# Sheet1.net
KiCad netlist of a schematic drawn in Altium Designer
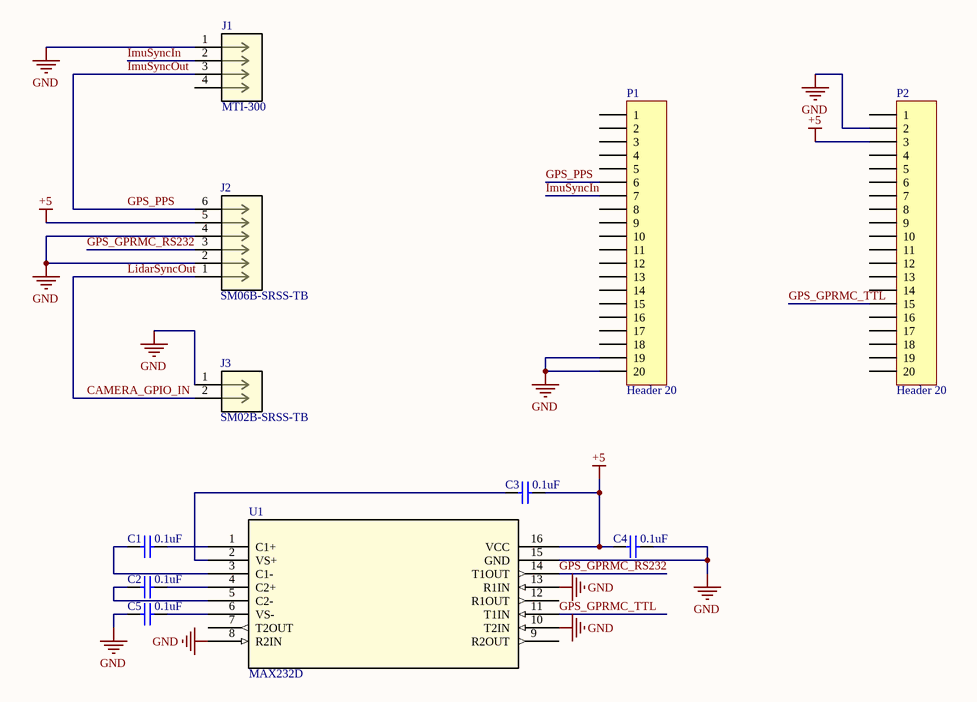
[diagram p0: Sheet1.SchDoc]

(export (version "E")
  (design (tool "Eeschema 10.0.6"))
  (components
    (comp (ref "C1")
      (value "0.1uF")
      (footprint "6-0805_N")
      (description "Capacitor")
      (fields (field (name "Comment") "Cap") (field (name "PUBLISHER") "Altium Limited"))
      (libsource (lib "Miscellaneous Devices") (part "Cap"))
    )
    (comp (ref "C2")
      (value "0.1uF")
      (footprint "6-0805_N")
      (description "Capacitor")
      (fields (field (name "Comment") "Cap") (field (name "PUBLISHER") "Altium Limited"))
      (libsource (lib "Miscellaneous Devices") (part "Cap"))
    )
    (comp (ref "C3")
      (value "0.1uF")
      (footprint "6-0805_N")
      (description "Capacitor")
      (fields (field (name "Comment") "Cap") (field (name "PUBLISHER") "Altium Limited"))
      (libsource (lib "Miscellaneous Devices") (part "Cap"))
    )
    (comp (ref "C4")
      (value "0.1uF")
      (footprint "6-0805_N")
      (description "Capacitor")
      (fields (field (name "Comment") "Cap") (field (name "PUBLISHER") "Altium Limited"))
      (libsource (lib "Miscellaneous Devices") (part "Cap"))
    )
    (comp (ref "C5")
      (value "0.1uF")
      (footprint "6-0805_N")
      (description "Capacitor")
      (fields (field (name "Comment") "Cap") (field (name "PUBLISHER") "Altium Limited"))
      (libsource (lib "Miscellaneous Devices") (part "Cap"))
    )
    (comp (ref "J1")
      (value "MTI-300")
      (footprint "CONN_SM04B-SRSS-TB_JST")
      (description "No Description Available")
      (libsource (lib "SM04B-SRSS-TB") (part "SM04B-SRSS-TB"))
    )
    (comp (ref "J2")
      (value "SM06B-SRSS-TB")
      (footprint "CONN_SM06B-SRSS-TB_JST")
      (description "No Description Available")
      (libsource (lib "SM06B-SRSS-TBLFSN") (part "SM06B-SRSS-TBLFSN"))
    )
    (comp (ref "J3")
      (value "SM02B-SRSS-TB")
      (footprint "CONN_SM02B-SRSS-TB_JST")
      (description "No Description Available")
      (libsource (lib "SM02B-SRSS-TB") (part "SM02B-SRSS-TB"))
    )
    (comp (ref "P1")
      (value "Header 20")
      (footprint "HDR1X20")
      (description "Header, 20-Pin")
      (fields (field (name "PUBLISHER") "Altium Limited"))
      (libsource (lib "Miscellaneous Connectors") (part "Header 20"))
    )
    (comp (ref "P2")
      (value "Header 20")
      (footprint "HDR1X20")
      (description "Header, 20-Pin")
      (fields (field (name "PUBLISHER") "Altium Limited"))
      (libsource (lib "Miscellaneous Connectors") (part "Header 20"))
    )
    (comp (ref "U1")
      (value "MAX232D")
      (footprint "D16")
      (description "No Description Available")
      (libsource (lib "MAX232D") (part "MAX232D"))
    )
  )
  (nets
    (net (code "1") (name "+5") (class "Default")
      (node (ref "C3") (pin "1") (pinfunction "1_1") (pintype "passive"))
      (node (ref "C4") (pin "2") (pinfunction "2_2") (pintype "passive"))
      (node (ref "J2") (pin "5") (pinfunction "5_5") (pintype "passive"))
      (node (ref "P2") (pin "3") (pinfunction "3_3") (pintype "passive"))
      (node (ref "U1") (pin "16") (pinfunction "VCC_16") (pintype "power_in"))
    )
    (net (code "2") (name "/CAMERA_GPIO_IN") (class "Default")
      (node (ref "J2") (pin "1") (pinfunction "1_1") (pintype "passive"))
      (node (ref "J3") (pin "2") (pinfunction "2_2") (pintype "passive"))
    )
    (net (code "3") (name "/GPS_GPRMC_RS232") (class "Default")
      (node (ref "J2") (pin "3") (pinfunction "3_3") (pintype "passive"))
      (node (ref "U1") (pin "14") (pinfunction "T1OUT_14") (pintype "output"))
    )
    (net (code "4") (name "/GPS_GPRMC_TTL") (class "Default")
      (node (ref "P2") (pin "15") (pinfunction "15_15") (pintype "passive"))
      (node (ref "U1") (pin "11") (pinfunction "T1IN_11") (pintype "input"))
    )
    (net (code "5") (name "/GPS_PPS") (class "Default")
      (node (ref "J1") (pin "3") (pinfunction "3_3") (pintype "passive"))
      (node (ref "J2") (pin "6") (pinfunction "6_6") (pintype "passive"))
      (node (ref "P1") (pin "6") (pinfunction "6_6") (pintype "passive"))
    )
    (net (code "6") (name "/ImuSyncIn") (class "Default")
      (node (ref "J1") (pin "2") (pinfunction "2_2") (pintype "passive"))
      (node (ref "P1") (pin "7") (pinfunction "7_7") (pintype "passive"))
    )
    (net (code "7") (name "GND") (class "Default")
      (node (ref "C4") (pin "1") (pinfunction "1_1") (pintype "passive"))
      (node (ref "C5") (pin "2") (pinfunction "2_2") (pintype "passive"))
      (node (ref "J1") (pin "1") (pinfunction "1_1") (pintype "passive"))
      (node (ref "J2") (pin "2") (pinfunction "2_2") (pintype "passive"))
      (node (ref "J2") (pin "4") (pinfunction "4_4") (pintype "passive"))
      (node (ref "J3") (pin "1") (pinfunction "1_1") (pintype "passive"))
      (node (ref "P1") (pin "19") (pinfunction "19_19") (pintype "passive"))
      (node (ref "P1") (pin "20") (pinfunction "20_20") (pintype "passive"))
      (node (ref "P2") (pin "2") (pinfunction "2_2") (pintype "passive"))
      (node (ref "U1") (pin "10") (pinfunction "T2IN_10") (pintype "input"))
      (node (ref "U1") (pin "13") (pinfunction "R1IN_13") (pintype "input"))
      (node (ref "U1") (pin "15") (pinfunction "GND_15") (pintype "power_in"))
      (node (ref "U1") (pin "8") (pinfunction "R2IN_8") (pintype "input"))
    )
    (net (code "8") (name "Net-(U1-C1+)") (class "Default")
      (node (ref "C1") (pin "1") (pinfunction "1_1") (pintype "passive"))
      (node (ref "U1") (pin "1") (pinfunction "C1+_1") (pintype "passive"))
    )
    (net (code "9") (name "Net-(U1-C1-)") (class "Default")
      (node (ref "C1") (pin "2") (pinfunction "2_2") (pintype "passive"))
      (node (ref "U1") (pin "3") (pinfunction "C1-_3") (pintype "passive"))
    )
    (net (code "10") (name "Net-(U1-C2+)") (class "Default")
      (node (ref "C2") (pin "1") (pinfunction "1_1") (pintype "passive"))
      (node (ref "U1") (pin "4") (pinfunction "C2+_4") (pintype "passive"))
    )
    (net (code "11") (name "Net-(U1-C2-)") (class "Default")
      (node (ref "C2") (pin "2") (pinfunction "2_2") (pintype "passive"))
      (node (ref "U1") (pin "5") (pinfunction "C2-_5") (pintype "passive"))
    )
    (net (code "12") (name "Net-(U1-VS+)") (class "Default")
      (node (ref "C3") (pin "2") (pinfunction "2_2") (pintype "passive"))
      (node (ref "U1") (pin "2") (pinfunction "VS+_2") (pintype "passive"))
    )
    (net (code "13") (name "Net-(U1-VS-)") (class "Default")
      (node (ref "C5") (pin "1") (pinfunction "1_1") (pintype "passive"))
      (node (ref "U1") (pin "6") (pinfunction "VS-_6") (pintype "passive"))
    )
    (net (code "14") (name "unconnected-(J1-Pad4)") (class "Default")
      (node (ref "J1") (pin "4") (pinfunction "4_4") (pintype "passive"))
    )
    (net (code "15") (name "unconnected-(P1-Pad1)") (class "Default")
      (node (ref "P1") (pin "1") (pinfunction "1_1") (pintype "passive"))
    )
    (net (code "16") (name "unconnected-(P1-Pad2)") (class "Default")
      (node (ref "P1") (pin "2") (pinfunction "2_2") (pintype "passive"))
    )
    (net (code "17") (name "unconnected-(P1-Pad3)") (class "Default")
      (node (ref "P1") (pin "3") (pinfunction "3_3") (pintype "passive"))
    )
    (net (code "18") (name "unconnected-(P1-Pad4)") (class "Default")
      (node (ref "P1") (pin "4") (pinfunction "4_4") (pintype "passive"))
    )
    (net (code "19") (name "unconnected-(P1-Pad5)") (class "Default")
      (node (ref "P1") (pin "5") (pinfunction "5_5") (pintype "passive"))
    )
    (net (code "20") (name "unconnected-(P1-Pad8)") (class "Default")
      (node (ref "P1") (pin "8") (pinfunction "8_8") (pintype "passive"))
    )
    (net (code "21") (name "unconnected-(P1-Pad9)") (class "Default")
      (node (ref "P1") (pin "9") (pinfunction "9_9") (pintype "passive"))
    )
    (net (code "22") (name "unconnected-(P1-Pad10)") (class "Default")
      (node (ref "P1") (pin "10") (pinfunction "10_10") (pintype "passive"))
    )
    (net (code "23") (name "unconnected-(P1-Pad11)") (class "Default")
      (node (ref "P1") (pin "11") (pinfunction "11_11") (pintype "passive"))
    )
    (net (code "24") (name "unconnected-(P1-Pad12)") (class "Default")
      (node (ref "P1") (pin "12") (pinfunction "12_12") (pintype "passive"))
    )
    (net (code "25") (name "unconnected-(P1-Pad13)") (class "Default")
      (node (ref "P1") (pin "13") (pinfunction "13_13") (pintype "passive"))
    )
    (net (code "26") (name "unconnected-(P1-Pad14)") (class "Default")
      (node (ref "P1") (pin "14") (pinfunction "14_14") (pintype "passive"))
    )
    (net (code "27") (name "unconnected-(P1-Pad15)") (class "Default")
      (node (ref "P1") (pin "15") (pinfunction "15_15") (pintype "passive"))
    )
    (net (code "28") (name "unconnected-(P1-Pad16)") (class "Default")
      (node (ref "P1") (pin "16") (pinfunction "16_16") (pintype "passive"))
    )
    (net (code "29") (name "unconnected-(P1-Pad17)") (class "Default")
      (node (ref "P1") (pin "17") (pinfunction "17_17") (pintype "passive"))
    )
    (net (code "30") (name "unconnected-(P1-Pad18)") (class "Default")
      (node (ref "P1") (pin "18") (pinfunction "18_18") (pintype "passive"))
    )
    (net (code "31") (name "unconnected-(P2-Pad1)") (class "Default")
      (node (ref "P2") (pin "1") (pinfunction "1_1") (pintype "passive"))
    )
    (net (code "32") (name "unconnected-(P2-Pad4)") (class "Default")
      (node (ref "P2") (pin "4") (pinfunction "4_4") (pintype "passive"))
    )
    (net (code "33") (name "unconnected-(P2-Pad5)") (class "Default")
      (node (ref "P2") (pin "5") (pinfunction "5_5") (pintype "passive"))
    )
    (net (code "34") (name "unconnected-(P2-Pad6)") (class "Default")
      (node (ref "P2") (pin "6") (pinfunction "6_6") (pintype "passive"))
    )
    (net (code "35") (name "unconnected-(P2-Pad7)") (class "Default")
      (node (ref "P2") (pin "7") (pinfunction "7_7") (pintype "passive"))
    )
    (net (code "36") (name "unconnected-(P2-Pad8)") (class "Default")
      (node (ref "P2") (pin "8") (pinfunction "8_8") (pintype "passive"))
    )
    (net (code "37") (name "unconnected-(P2-Pad9)") (class "Default")
      (node (ref "P2") (pin "9") (pinfunction "9_9") (pintype "passive"))
    )
    (net (code "38") (name "unconnected-(P2-Pad10)") (class "Default")
      (node (ref "P2") (pin "10") (pinfunction "10_10") (pintype "passive"))
    )
    (net (code "39") (name "unconnected-(P2-Pad11)") (class "Default")
      (node (ref "P2") (pin "11") (pinfunction "11_11") (pintype "passive"))
    )
    (net (code "40") (name "unconnected-(P2-Pad12)") (class "Default")
      (node (ref "P2") (pin "12") (pinfunction "12_12") (pintype "passive"))
    )
    (net (code "41") (name "unconnected-(P2-Pad13)") (class "Default")
      (node (ref "P2") (pin "13") (pinfunction "13_13") (pintype "passive"))
    )
    (net (code "42") (name "unconnected-(P2-Pad14)") (class "Default")
      (node (ref "P2") (pin "14") (pinfunction "14_14") (pintype "passive"))
    )
    (net (code "43") (name "unconnected-(P2-Pad16)") (class "Default")
      (node (ref "P2") (pin "16") (pinfunction "16_16") (pintype "passive"))
    )
    (net (code "44") (name "unconnected-(P2-Pad17)") (class "Default")
      (node (ref "P2") (pin "17") (pinfunction "17_17") (pintype "passive"))
    )
    (net (code "45") (name "unconnected-(P2-Pad18)") (class "Default")
      (node (ref "P2") (pin "18") (pinfunction "18_18") (pintype "passive"))
    )
    (net (code "46") (name "unconnected-(P2-Pad19)") (class "Default")
      (node (ref "P2") (pin "19") (pinfunction "19_19") (pintype "passive"))
    )
    (net (code "47") (name "unconnected-(P2-Pad20)") (class "Default")
      (node (ref "P2") (pin "20") (pinfunction "20_20") (pintype "passive"))
    )
    (net (code "48") (name "unconnected-(U1-R1OUT-Pad12)") (class "Default")
      (node (ref "U1") (pin "12") (pinfunction "R1OUT_12") (pintype "output"))
    )
    (net (code "49") (name "unconnected-(U1-R2OUT-Pad9)") (class "Default")
      (node (ref "U1") (pin "9") (pinfunction "R2OUT_9") (pintype "output"))
    )
    (net (code "50") (name "unconnected-(U1-T2OUT-Pad7)") (class "Default")
      (node (ref "U1") (pin "7") (pinfunction "T2OUT_7") (pintype "output"))
    )
  )
)
